# M220A.net
KiCad netlist of a schematic drawn in EAGLE
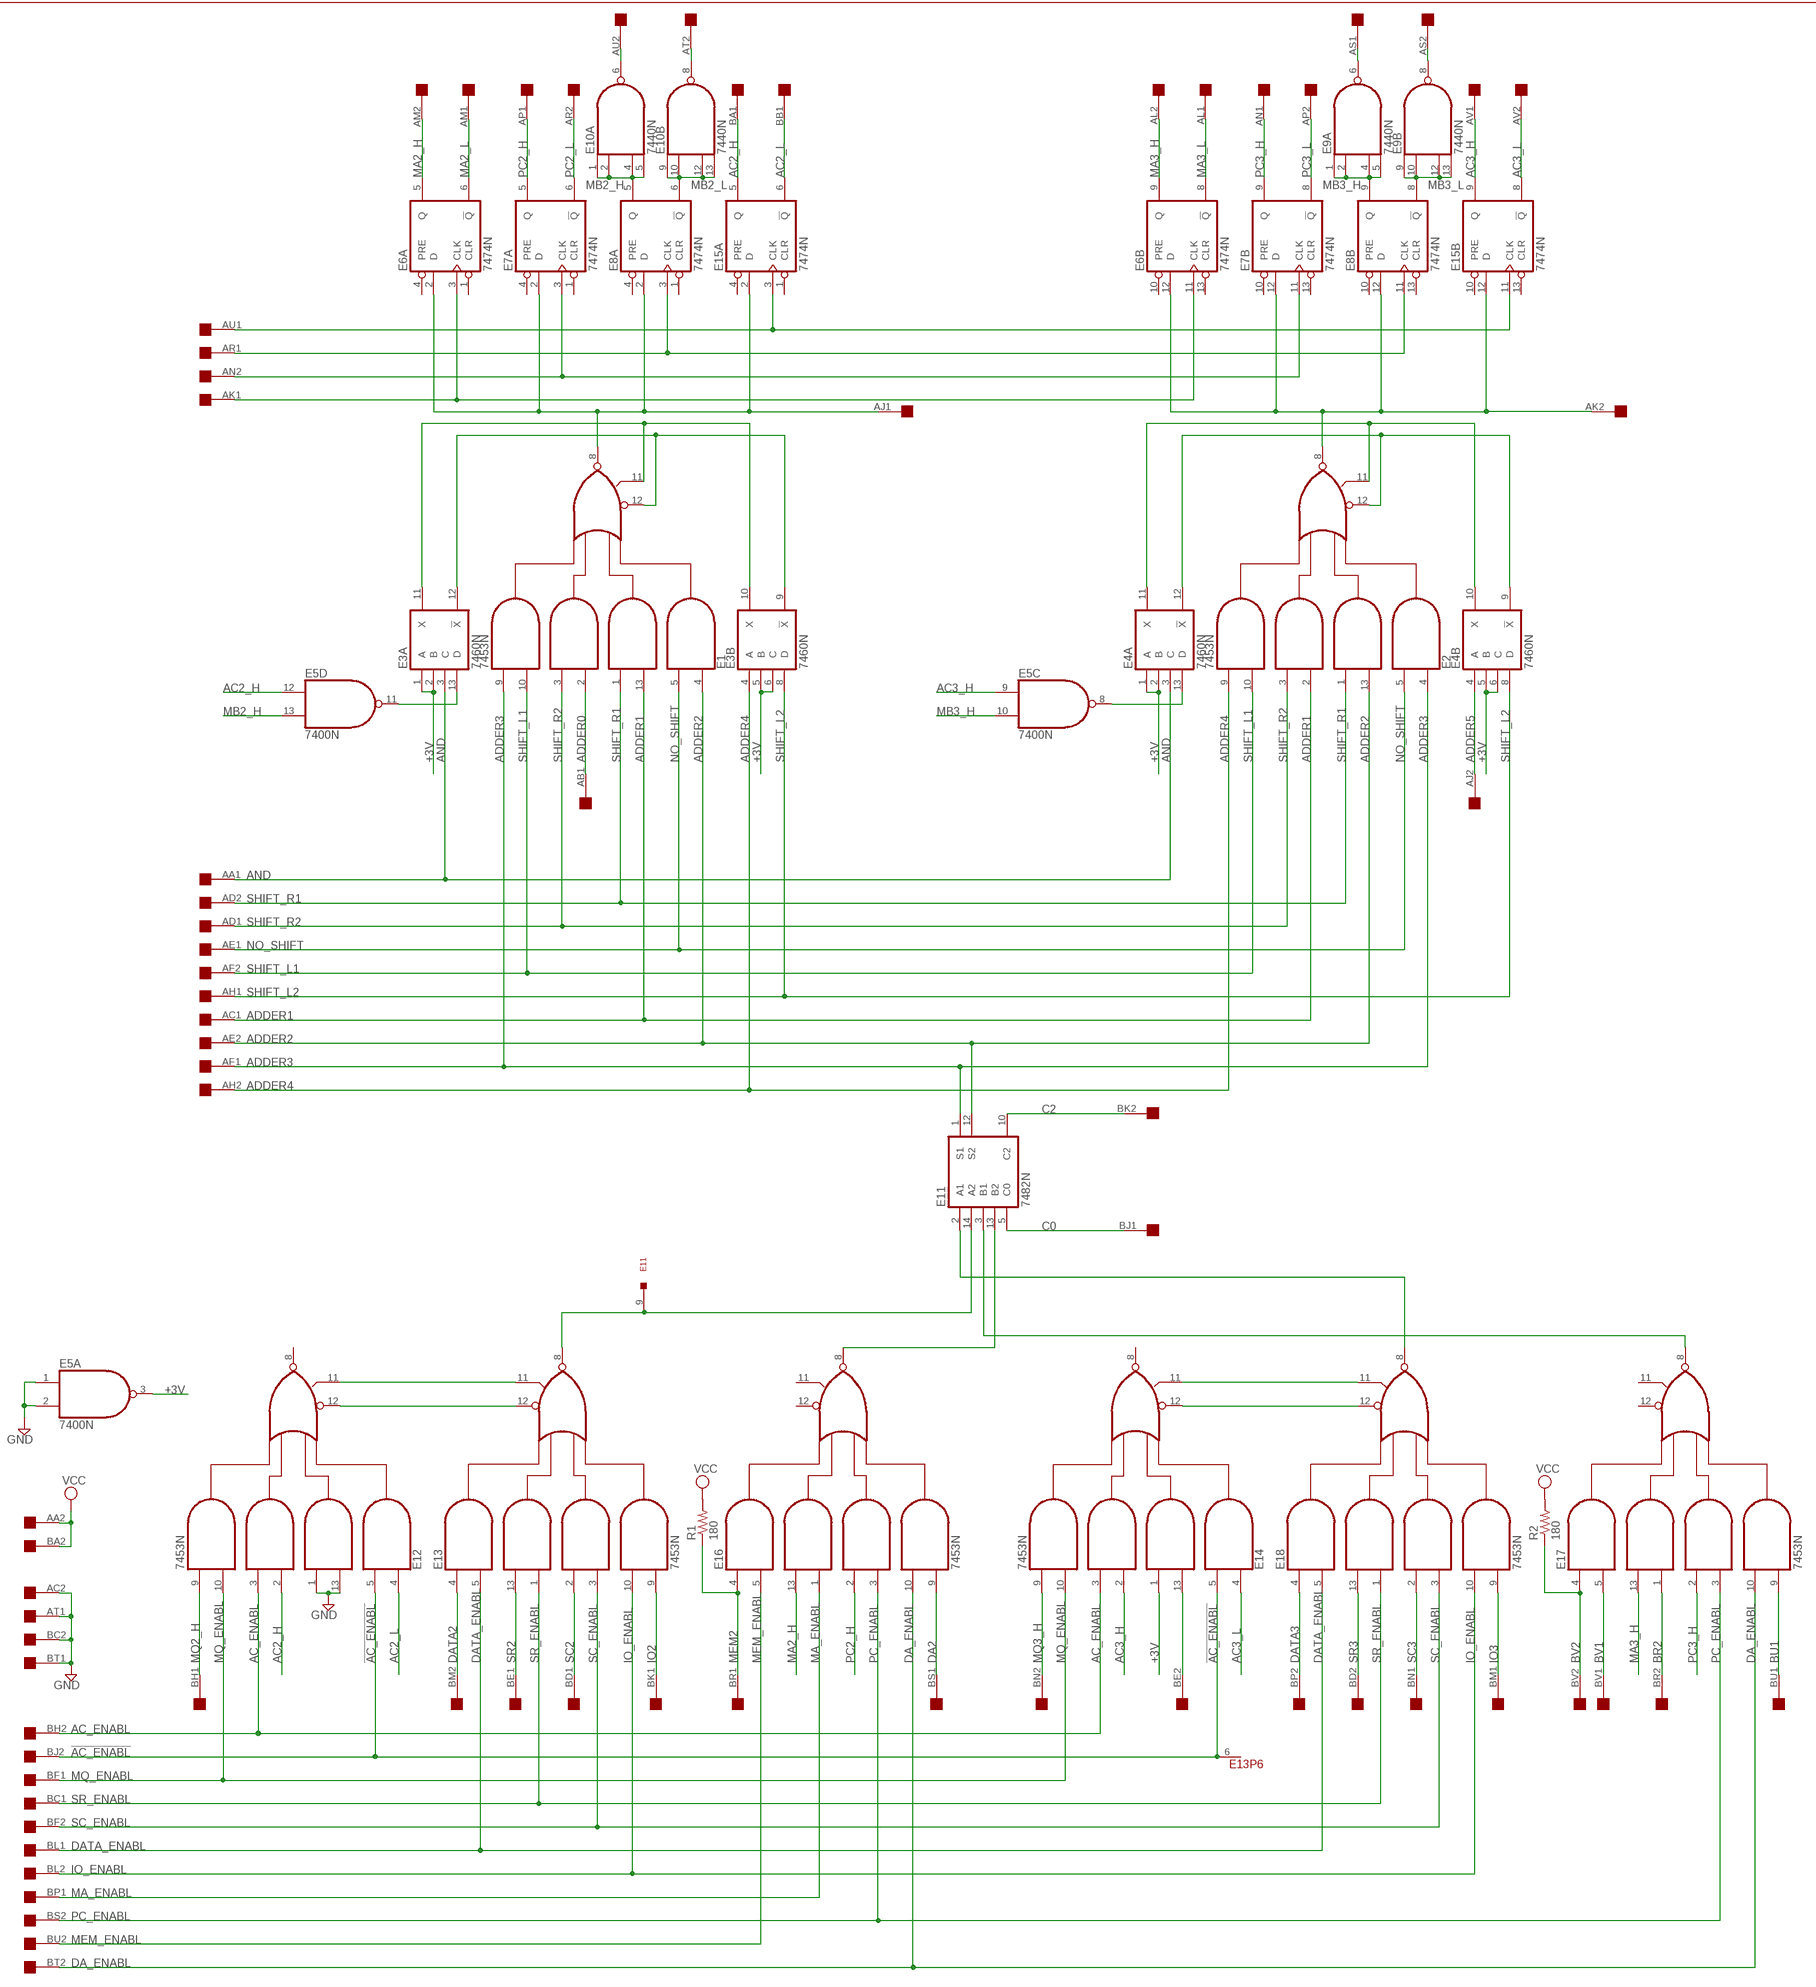
[diagram p0: schematic, sheet 1, part 1 of 2]
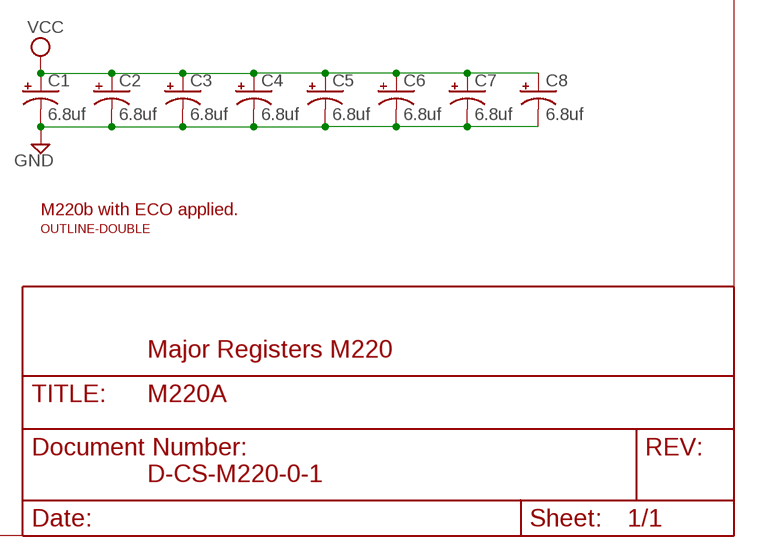
[diagram p1: schematic, sheet 1, part 2 of 2]

(export (version "E")
  (design (tool "Eeschema 10.0.6"))
  (components
    (comp (ref "C1")
      (value "6.8uf")
      (footprint "eagle-import:E15-5")
      (libsource (lib "eagle-import") (part "CPOL-USE15-5AXIAL"))
    )
    (comp (ref "C2")
      (value "6.8uf")
      (footprint "eagle-import:E15-5")
      (libsource (lib "eagle-import") (part "CPOL-USE15-5AXIAL"))
    )
    (comp (ref "C3")
      (value "6.8uf")
      (footprint "eagle-import:E15-5")
      (libsource (lib "eagle-import") (part "CPOL-USE15-5AXIAL"))
    )
    (comp (ref "C4")
      (value "6.8uf")
      (footprint "eagle-import:E15-5")
      (libsource (lib "eagle-import") (part "CPOL-USE15-5AXIAL"))
    )
    (comp (ref "C5")
      (value "6.8uf")
      (footprint "eagle-import:E15-5")
      (libsource (lib "eagle-import") (part "CPOL-USE15-5AXIAL"))
    )
    (comp (ref "C6")
      (value "6.8uf")
      (footprint "eagle-import:E15-5")
      (libsource (lib "eagle-import") (part "CPOL-USE15-5AXIAL"))
    )
    (comp (ref "C7")
      (value "6.8uf")
      (footprint "eagle-import:E15-5")
      (libsource (lib "eagle-import") (part "CPOL-USE15-5AXIAL"))
    )
    (comp (ref "C8")
      (value "6.8uf")
      (footprint "eagle-import:E15-5")
      (libsource (lib "eagle-import") (part "CPOL-USE15-5AXIAL"))
    )
    (comp (ref "E1")
      (value "7453N")
      (footprint "eagle-import:DIL14")
      (libsource (lib "eagle-import") (part "7453N"))
    )
    (comp (ref "E2")
      (value "7453N")
      (footprint "eagle-import:DIL14")
      (libsource (lib "eagle-import") (part "7453N"))
    )
    (comp (ref "E3")
      (value "7460N")
      (footprint "eagle-import:DIL14")
      (libsource (lib "eagle-import") (part "7460N"))
    )
    (comp (ref "E4")
      (value "7460N")
      (footprint "eagle-import:DIL14")
      (libsource (lib "eagle-import") (part "7460N"))
    )
    (comp (ref "E5")
      (value "7400N")
      (footprint "eagle-import:DIL14")
      (libsource (lib "eagle-import") (part "7400N"))
    )
    (comp (ref "E6")
      (value "7474N")
      (footprint "eagle-import:DIL14")
      (libsource (lib "eagle-import") (part "7474NS"))
    )
    (comp (ref "E7")
      (value "7474N")
      (footprint "eagle-import:DIL14")
      (libsource (lib "eagle-import") (part "7474NS"))
    )
    (comp (ref "E8")
      (value "7474N")
      (footprint "eagle-import:DIL14")
      (libsource (lib "eagle-import") (part "7474NS"))
    )
    (comp (ref "E9")
      (value "7440N")
      (footprint "eagle-import:DIL14")
      (libsource (lib "eagle-import") (part "7420NS"))
    )
    (comp (ref "E10")
      (value "7440N")
      (footprint "eagle-import:DIL14")
      (libsource (lib "eagle-import") (part "7420NS"))
    )
    (comp (ref "E11")
      (value "7482N")
      (footprint "eagle-import:DIL14")
      (libsource (lib "eagle-import") (part "7482N"))
    )
    (comp (ref "E12")
      (value "7453N")
      (footprint "eagle-import:DIL14")
      (libsource (lib "eagle-import") (part "7453N"))
    )
    (comp (ref "E13")
      (value "7453N")
      (footprint "eagle-import:DIL14")
      (libsource (lib "eagle-import") (part "7453N"))
    )
    (comp (ref "E14")
      (value "7453N")
      (footprint "eagle-import:DIL14")
      (libsource (lib "eagle-import") (part "7453N"))
    )
    (comp (ref "E15")
      (value "7474N")
      (footprint "eagle-import:DIL14")
      (libsource (lib "eagle-import") (part "7474NS"))
    )
    (comp (ref "E16")
      (value "7453N")
      (footprint "eagle-import:DIL14")
      (libsource (lib "eagle-import") (part "7453N"))
    )
    (comp (ref "E17")
      (value "7453N")
      (footprint "eagle-import:DIL14")
      (libsource (lib "eagle-import") (part "7453N"))
    )
    (comp (ref "E18")
      (value "7453N")
      (footprint "eagle-import:DIL14")
      (libsource (lib "eagle-import") (part "7453N"))
    )
    (comp (ref "R1")
      (value "180")
      (footprint "eagle-import:0207_10")
      (libsource (lib "eagle-import") (part "R-US_0207/10"))
    )
    (comp (ref "R2")
      (value "180")
      (footprint "eagle-import:0207_10")
      (libsource (lib "eagle-import") (part "R-US_0207/10"))
    )
    (comp (ref "U$1")
      (value "DOUBLE")
      (footprint "eagle-import:EDGE-CON4")
      (libsource (lib "eagle-import") (part "DOUBLE"))
    )
    (comp (ref "U$2")
      (value "OUTLINE-DOUBLE")
      (footprint "eagle-import:DOUBLE")
      (libsource (lib "eagle-import") (part "OUTLINE-DOUBLE"))
    )
  )
  (nets
    (net (code "1") (name "/+3V") (class "Default")
      (node (ref "E14") (pin "1") (pinfunction "I4_1") (pintype "input"))
      (node (ref "E3") (pin "1") (pinfunction "A_1") (pintype "input"))
      (node (ref "E3") (pin "2") (pinfunction "B_2") (pintype "input"))
      (node (ref "E3") (pin "5") (pinfunction "B_5") (pintype "input"))
      (node (ref "E3") (pin "6") (pinfunction "C_6") (pintype "input"))
      (node (ref "E4") (pin "1") (pinfunction "A_1") (pintype "input"))
      (node (ref "E4") (pin "2") (pinfunction "B_2") (pintype "input"))
      (node (ref "E4") (pin "5") (pinfunction "B_5") (pintype "input"))
      (node (ref "E4") (pin "6") (pinfunction "C_6") (pintype "input"))
      (node (ref "E5") (pin "3") (pinfunction "O_3") (pintype "output"))
    )
    (net (code "2") (name "/AC2_H") (class "Default")
      (node (ref "E12") (pin "2") (pinfunction "I5_2") (pintype "input"))
      (node (ref "E15") (pin "5") (pinfunction "Q_5") (pintype "output"))
      (node (ref "E5") (pin "12") (pinfunction "I0_12") (pintype "input"))
      (node (ref "U$1") (pin "BA1") (pinfunction "1_BA1") (pintype "bidirectional"))
    )
    (net (code "3") (name "/AC2_L") (class "Default")
      (node (ref "E12") (pin "4") (pinfunction "I1_4") (pintype "input"))
      (node (ref "E15") (pin "6") (pinfunction "~{Q}_6") (pintype "output"))
      (node (ref "U$1") (pin "BB1") (pinfunction "1_BB1") (pintype "bidirectional"))
    )
    (net (code "4") (name "/AC3_H") (class "Default")
      (node (ref "E14") (pin "2") (pinfunction "I5_2") (pintype "input"))
      (node (ref "E15") (pin "9") (pinfunction "Q_9") (pintype "output"))
      (node (ref "E5") (pin "9") (pinfunction "I0_9") (pintype "input"))
      (node (ref "U$1") (pin "AV1") (pinfunction "1_AV1") (pintype "bidirectional"))
    )
    (net (code "5") (name "/AC3_L") (class "Default")
      (node (ref "E14") (pin "4") (pinfunction "I1_4") (pintype "input"))
      (node (ref "E15") (pin "8") (pinfunction "~{Q}_8") (pintype "output"))
      (node (ref "U$1") (pin "AV2") (pinfunction "1_AV2") (pintype "bidirectional"))
    )
    (net (code "6") (name "/AC_ENABL") (class "Default")
      (node (ref "E12") (pin "3") (pinfunction "I6_3") (pintype "input"))
      (node (ref "E14") (pin "3") (pinfunction "I6_3") (pintype "input"))
      (node (ref "U$1") (pin "BH2") (pinfunction "1_BH2") (pintype "bidirectional"))
    )
    (net (code "7") (name "/ADDER0") (class "Default")
      (node (ref "E1") (pin "2") (pinfunction "I5_2") (pintype "input"))
      (node (ref "U$1") (pin "AB1") (pinfunction "1_AB1") (pintype "bidirectional"))
    )
    (net (code "8") (name "/ADDER1") (class "Default")
      (node (ref "E1") (pin "13") (pinfunction "I3_13") (pintype "input"))
      (node (ref "E2") (pin "2") (pinfunction "I5_2") (pintype "input"))
      (node (ref "U$1") (pin "AC1") (pinfunction "1_AC1") (pintype "bidirectional"))
    )
    (net (code "9") (name "/ADDER2") (class "Default")
      (node (ref "E1") (pin "4") (pinfunction "I1_4") (pintype "input"))
      (node (ref "E11") (pin "12") (pinfunction "S2_12") (pintype "output"))
      (node (ref "E2") (pin "13") (pinfunction "I3_13") (pintype "input"))
      (node (ref "U$1") (pin "AE2") (pinfunction "1_AE2") (pintype "bidirectional"))
    )
    (net (code "10") (name "/ADDER3") (class "Default")
      (node (ref "E1") (pin "9") (pinfunction "I8_9") (pintype "input"))
      (node (ref "E11") (pin "1") (pinfunction "S1_1") (pintype "output"))
      (node (ref "E2") (pin "4") (pinfunction "I1_4") (pintype "input"))
      (node (ref "U$1") (pin "AF1") (pinfunction "1_AF1") (pintype "bidirectional"))
    )
    (net (code "11") (name "/ADDER4") (class "Default")
      (node (ref "E2") (pin "9") (pinfunction "I8_9") (pintype "input"))
      (node (ref "E3") (pin "4") (pinfunction "A_4") (pintype "input"))
      (node (ref "U$1") (pin "AH2") (pinfunction "1_AH2") (pintype "bidirectional"))
    )
    (net (code "12") (name "/ADDER5") (class "Default")
      (node (ref "E4") (pin "4") (pinfunction "A_4") (pintype "input"))
      (node (ref "U$1") (pin "AJ2") (pinfunction "1_AJ2") (pintype "bidirectional"))
    )
    (net (code "13") (name "/AND") (class "Default")
      (node (ref "E3") (pin "3") (pinfunction "C_3") (pintype "input"))
      (node (ref "E4") (pin "3") (pinfunction "C_3") (pintype "input"))
      (node (ref "U$1") (pin "AA1") (pinfunction "1_AA1") (pintype "bidirectional"))
    )
    (net (code "14") (name "/BR2") (class "Default")
      (node (ref "E17") (pin "1") (pinfunction "I4_1") (pintype "input"))
      (node (ref "U$1") (pin "BR2") (pinfunction "1_BR2") (pintype "bidirectional"))
    )
    (net (code "15") (name "/BU1") (class "Default")
      (node (ref "E17") (pin "9") (pinfunction "I8_9") (pintype "input"))
      (node (ref "U$1") (pin "BU1") (pinfunction "1_BU1") (pintype "bidirectional"))
    )
    (net (code "16") (name "/BV1") (class "Default")
      (node (ref "E17") (pin "5") (pinfunction "I2_5") (pintype "input"))
      (node (ref "U$1") (pin "BV1") (pinfunction "1_BV1") (pintype "bidirectional"))
    )
    (net (code "17") (name "/BV2") (class "Default")
      (node (ref "E17") (pin "4") (pinfunction "I1_4") (pintype "input"))
      (node (ref "R2") (pin "1") (pinfunction "1_1") (pintype "passive"))
      (node (ref "U$1") (pin "BV2") (pinfunction "1_BV2") (pintype "bidirectional"))
    )
    (net (code "18") (name "/C0") (class "Default")
      (node (ref "E11") (pin "5") (pinfunction "C0_5") (pintype "input"))
      (node (ref "U$1") (pin "BJ1") (pinfunction "1_BJ1") (pintype "bidirectional"))
    )
    (net (code "19") (name "/C2") (class "Default")
      (node (ref "E11") (pin "10") (pinfunction "C2_10") (pintype "output"))
      (node (ref "U$1") (pin "BK2") (pinfunction "1_BK2") (pintype "bidirectional"))
    )
    (net (code "20") (name "/DA2") (class "Default")
      (node (ref "E16") (pin "9") (pinfunction "I8_9") (pintype "input"))
      (node (ref "U$1") (pin "BS1") (pinfunction "1_BS1") (pintype "bidirectional"))
    )
    (net (code "21") (name "/DATA2") (class "Default")
      (node (ref "E13") (pin "4") (pinfunction "I1_4") (pintype "input"))
      (node (ref "U$1") (pin "BM2") (pinfunction "1_BM2") (pintype "bidirectional"))
    )
    (net (code "22") (name "/DATA3") (class "Default")
      (node (ref "E18") (pin "4") (pinfunction "I1_4") (pintype "input"))
      (node (ref "U$1") (pin "BP2") (pinfunction "1_BP2") (pintype "bidirectional"))
    )
    (net (code "23") (name "/DATA_ENABL") (class "Default")
      (node (ref "E13") (pin "5") (pinfunction "I2_5") (pintype "input"))
      (node (ref "E18") (pin "5") (pinfunction "I2_5") (pintype "input"))
      (node (ref "U$1") (pin "BL1") (pinfunction "1_BL1") (pintype "bidirectional"))
    )
    (net (code "24") (name "/DA_ENABL") (class "Default")
      (node (ref "E16") (pin "10") (pinfunction "I7_10") (pintype "input"))
      (node (ref "E17") (pin "10") (pinfunction "I7_10") (pintype "input"))
      (node (ref "U$1") (pin "BT2") (pinfunction "1_BT2") (pintype "bidirectional"))
    )
    (net (code "25") (name "/IO2") (class "Default")
      (node (ref "E13") (pin "9") (pinfunction "I8_9") (pintype "input"))
      (node (ref "U$1") (pin "BK1") (pinfunction "1_BK1") (pintype "bidirectional"))
    )
    (net (code "26") (name "/IO3") (class "Default")
      (node (ref "E18") (pin "9") (pinfunction "I8_9") (pintype "input"))
      (node (ref "U$1") (pin "BM1") (pinfunction "1_BM1") (pintype "bidirectional"))
    )
    (net (code "27") (name "/IO_ENABL") (class "Default")
      (node (ref "E13") (pin "10") (pinfunction "I7_10") (pintype "input"))
      (node (ref "E18") (pin "10") (pinfunction "I7_10") (pintype "input"))
      (node (ref "U$1") (pin "BL2") (pinfunction "1_BL2") (pintype "bidirectional"))
    )
    (net (code "28") (name "/MA2_H") (class "Default")
      (node (ref "E16") (pin "13") (pinfunction "I3_13") (pintype "input"))
      (node (ref "E6") (pin "5") (pinfunction "Q_5") (pintype "output"))
      (node (ref "U$1") (pin "AM2") (pinfunction "1_AM2") (pintype "bidirectional"))
    )
    (net (code "29") (name "/MA2_L") (class "Default")
      (node (ref "E6") (pin "6") (pinfunction "~{Q}_6") (pintype "output"))
      (node (ref "U$1") (pin "AM1") (pinfunction "1_AM1") (pintype "bidirectional"))
    )
    (net (code "30") (name "/MA3_H") (class "Default")
      (node (ref "E17") (pin "13") (pinfunction "I3_13") (pintype "input"))
      (node (ref "E6") (pin "9") (pinfunction "Q_9") (pintype "output"))
      (node (ref "U$1") (pin "AL2") (pinfunction "1_AL2") (pintype "bidirectional"))
    )
    (net (code "31") (name "/MA3_L") (class "Default")
      (node (ref "E6") (pin "8") (pinfunction "~{Q}_8") (pintype "output"))
      (node (ref "U$1") (pin "AL1") (pinfunction "1_AL1") (pintype "bidirectional"))
    )
    (net (code "32") (name "/MA_ENABL") (class "Default")
      (node (ref "E16") (pin "1") (pinfunction "I4_1") (pintype "input"))
      (node (ref "U$1") (pin "BP1") (pinfunction "1_BP1") (pintype "bidirectional"))
    )
    (net (code "33") (name "/MB2_H") (class "Default")
      (node (ref "E10") (pin "1") (pinfunction "I0_1") (pintype "input"))
      (node (ref "E10") (pin "2") (pinfunction "I1_2") (pintype "input"))
      (node (ref "E10") (pin "4") (pinfunction "I2_4") (pintype "input"))
      (node (ref "E10") (pin "5") (pinfunction "I3_5") (pintype "input"))
      (node (ref "E5") (pin "13") (pinfunction "I1_13") (pintype "input"))
      (node (ref "E8") (pin "5") (pinfunction "Q_5") (pintype "output"))
    )
    (net (code "34") (name "/MB2_L") (class "Default")
      (node (ref "E10") (pin "10") (pinfunction "I1_10") (pintype "input"))
      (node (ref "E10") (pin "12") (pinfunction "I2_12") (pintype "input"))
      (node (ref "E10") (pin "13") (pinfunction "I3_13") (pintype "input"))
      (node (ref "E10") (pin "9") (pinfunction "I0_9") (pintype "input"))
      (node (ref "E8") (pin "6") (pinfunction "~{Q}_6") (pintype "output"))
    )
    (net (code "35") (name "/MB3_H") (class "Default")
      (node (ref "E5") (pin "10") (pinfunction "I1_10") (pintype "input"))
      (node (ref "E8") (pin "9") (pinfunction "Q_9") (pintype "output"))
      (node (ref "E9") (pin "1") (pinfunction "I0_1") (pintype "input"))
      (node (ref "E9") (pin "2") (pinfunction "I1_2") (pintype "input"))
      (node (ref "E9") (pin "4") (pinfunction "I2_4") (pintype "input"))
      (node (ref "E9") (pin "5") (pinfunction "I3_5") (pintype "input"))
    )
    (net (code "36") (name "/MB3_L") (class "Default")
      (node (ref "E8") (pin "8") (pinfunction "~{Q}_8") (pintype "output"))
      (node (ref "E9") (pin "10") (pinfunction "I1_10") (pintype "input"))
      (node (ref "E9") (pin "12") (pinfunction "I2_12") (pintype "input"))
      (node (ref "E9") (pin "13") (pinfunction "I3_13") (pintype "input"))
      (node (ref "E9") (pin "9") (pinfunction "I0_9") (pintype "input"))
    )
    (net (code "37") (name "/MEM2") (class "Default")
      (node (ref "E16") (pin "4") (pinfunction "I1_4") (pintype "input"))
      (node (ref "R1") (pin "1") (pinfunction "1_1") (pintype "passive"))
      (node (ref "U$1") (pin "BR1") (pinfunction "1_BR1") (pintype "bidirectional"))
    )
    (net (code "38") (name "/MEM_ENABL") (class "Default")
      (node (ref "E16") (pin "5") (pinfunction "I2_5") (pintype "input"))
      (node (ref "U$1") (pin "BU2") (pinfunction "1_BU2") (pintype "bidirectional"))
    )
    (net (code "39") (name "/MQ2_H") (class "Default")
      (node (ref "E12") (pin "9") (pinfunction "I8_9") (pintype "input"))
      (node (ref "U$1") (pin "BH1") (pinfunction "1_BH1") (pintype "bidirectional"))
    )
    (net (code "40") (name "/MQ3_H") (class "Default")
      (node (ref "E14") (pin "9") (pinfunction "I8_9") (pintype "input"))
      (node (ref "U$1") (pin "BN2") (pinfunction "1_BN2") (pintype "bidirectional"))
    )
    (net (code "41") (name "/MQ_ENABL") (class "Default")
      (node (ref "E12") (pin "10") (pinfunction "I7_10") (pintype "input"))
      (node (ref "E14") (pin "10") (pinfunction "I7_10") (pintype "input"))
      (node (ref "U$1") (pin "BF1") (pinfunction "1_BF1") (pintype "bidirectional"))
    )
    (net (code "42") (name "/NO_SHIFT") (class "Default")
      (node (ref "E1") (pin "5") (pinfunction "I2_5") (pintype "input"))
      (node (ref "E2") (pin "5") (pinfunction "I2_5") (pintype "input"))
      (node (ref "U$1") (pin "AE1") (pinfunction "1_AE1") (pintype "bidirectional"))
    )
    (net (code "43") (name "/PC2_H") (class "Default")
      (node (ref "E16") (pin "2") (pinfunction "I5_2") (pintype "input"))
      (node (ref "E7") (pin "5") (pinfunction "Q_5") (pintype "output"))
      (node (ref "U$1") (pin "AP1") (pinfunction "1_AP1") (pintype "bidirectional"))
    )
    (net (code "44") (name "/PC2_L") (class "Default")
      (node (ref "E7") (pin "6") (pinfunction "~{Q}_6") (pintype "output"))
      (node (ref "U$1") (pin "AR2") (pinfunction "1_AR2") (pintype "bidirectional"))
    )
    (net (code "45") (name "/PC3_H") (class "Default")
      (node (ref "E17") (pin "2") (pinfunction "I5_2") (pintype "input"))
      (node (ref "E7") (pin "9") (pinfunction "Q_9") (pintype "output"))
      (node (ref "U$1") (pin "AN1") (pinfunction "1_AN1") (pintype "bidirectional"))
    )
    (net (code "46") (name "/PC3_L") (class "Default")
      (node (ref "E7") (pin "8") (pinfunction "~{Q}_8") (pintype "output"))
      (node (ref "U$1") (pin "AP2") (pinfunction "1_AP2") (pintype "bidirectional"))
    )
    (net (code "47") (name "/PC_ENABL") (class "Default")
      (node (ref "E16") (pin "3") (pinfunction "I6_3") (pintype "input"))
      (node (ref "E17") (pin "3") (pinfunction "I6_3") (pintype "input"))
      (node (ref "U$1") (pin "BS2") (pinfunction "1_BS2") (pintype "bidirectional"))
    )
    (net (code "48") (name "/SC2") (class "Default")
      (node (ref "E13") (pin "2") (pinfunction "I5_2") (pintype "input"))
      (node (ref "U$1") (pin "BD1") (pinfunction "1_BD1") (pintype "bidirectional"))
    )
    (net (code "49") (name "/SC3") (class "Default")
      (node (ref "E18") (pin "2") (pinfunction "I5_2") (pintype "input"))
      (node (ref "U$1") (pin "BN1") (pinfunction "1_BN1") (pintype "bidirectional"))
    )
    (net (code "50") (name "/SC_ENABL") (class "Default")
      (node (ref "E13") (pin "3") (pinfunction "I6_3") (pintype "input"))
      (node (ref "E18") (pin "3") (pinfunction "I6_3") (pintype "input"))
      (node (ref "U$1") (pin "BF2") (pinfunction "1_BF2") (pintype "bidirectional"))
    )
    (net (code "51") (name "/SHIFT_L1") (class "Default")
      (node (ref "E1") (pin "10") (pinfunction "I7_10") (pintype "input"))
      (node (ref "E2") (pin "10") (pinfunction "I7_10") (pintype "input"))
      (node (ref "U$1") (pin "AF2") (pinfunction "1_AF2") (pintype "bidirectional"))
    )
    (net (code "52") (name "/SHIFT_L2") (class "Default")
      (node (ref "E3") (pin "8") (pinfunction "D_8") (pintype "input"))
      (node (ref "E4") (pin "8") (pinfunction "D_8") (pintype "input"))
      (node (ref "U$1") (pin "AH1") (pinfunction "1_AH1") (pintype "bidirectional"))
    )
    (net (code "53") (name "/SHIFT_R1") (class "Default")
      (node (ref "E1") (pin "1") (pinfunction "I4_1") (pintype "input"))
      (node (ref "E2") (pin "1") (pinfunction "I4_1") (pintype "input"))
      (node (ref "U$1") (pin "AD2") (pinfunction "1_AD2") (pintype "bidirectional"))
    )
    (net (code "54") (name "/SHIFT_R2") (class "Default")
      (node (ref "E1") (pin "3") (pinfunction "I6_3") (pintype "input"))
      (node (ref "E2") (pin "3") (pinfunction "I6_3") (pintype "input"))
      (node (ref "U$1") (pin "AD1") (pinfunction "1_AD1") (pintype "bidirectional"))
    )
    (net (code "55") (name "/SR2") (class "Default")
      (node (ref "E13") (pin "13") (pinfunction "I3_13") (pintype "input"))
      (node (ref "U$1") (pin "BE1") (pinfunction "1_BE1") (pintype "bidirectional"))
    )
    (net (code "56") (name "/SR3") (class "Default")
      (node (ref "E18") (pin "13") (pinfunction "I3_13") (pintype "input"))
      (node (ref "U$1") (pin "BD2") (pinfunction "1_BD2") (pintype "bidirectional"))
    )
    (net (code "57") (name "/SR_ENABL") (class "Default")
      (node (ref "E13") (pin "1") (pinfunction "I4_1") (pintype "input"))
      (node (ref "E18") (pin "1") (pinfunction "I4_1") (pintype "input"))
      (node (ref "U$1") (pin "BC1") (pinfunction "1_BC1") (pintype "bidirectional"))
    )
    (net (code "58") (name "/~{AC_ENABL}") (class "Default")
      (node (ref "E12") (pin "5") (pinfunction "I2_5") (pintype "input"))
      (node (ref "E13") (pin "6") (pinfunction "SPARE_6") (pintype "passive"))
      (node (ref "E14") (pin "5") (pinfunction "I2_5") (pintype "input"))
      (node (ref "U$1") (pin "BJ2") (pinfunction "1_BJ2") (pintype "bidirectional"))
    )
    (net (code "59") (name "GND") (class "Default")
      (node (ref "C1") (pin "-") (pinfunction "-_-") (pintype "passive"))
      (node (ref "C2") (pin "-") (pinfunction "-_-") (pintype "passive"))
      (node (ref "C3") (pin "-") (pinfunction "-_-") (pintype "passive"))
      (node (ref "C4") (pin "-") (pinfunction "-_-") (pintype "passive"))
      (node (ref "C5") (pin "-") (pinfunction "-_-") (pintype "passive"))
      (node (ref "C6") (pin "-") (pinfunction "-_-") (pintype "passive"))
      (node (ref "C7") (pin "-") (pinfunction "-_-") (pintype "passive"))
      (node (ref "C8") (pin "-") (pinfunction "-_-") (pintype "passive"))
      (node (ref "E12") (pin "1") (pinfunction "I4_1") (pintype "input"))
      (node (ref "E12") (pin "13") (pinfunction "I3_13") (pintype "input"))
      (node (ref "E5") (pin "1") (pinfunction "I0_1") (pintype "input"))
      (node (ref "E5") (pin "2") (pinfunction "I1_2") (pintype "input"))
      (node (ref "U$1") (pin "AC2") (pinfunction "1_AC2") (pintype "bidirectional"))
      (node (ref "U$1") (pin "AT1") (pinfunction "1_AT1") (pintype "bidirectional"))
      (node (ref "U$1") (pin "BC2") (pinfunction "1_BC2") (pintype "bidirectional"))
      (node (ref "U$1") (pin "BT1") (pinfunction "1_BT1") (pintype "bidirectional"))
    )
    (net (code "60") (name "Net-(E1A-I9)") (class "Default")
      (node (ref "E1") (pin "12") (pinfunction "I9_12") (pintype "passive"))
      (node (ref "E3") (pin "12") (pinfunction "~{X}_12") (pintype "output"))
      (node (ref "E3") (pin "9") (pinfunction "~{X}_9") (pintype "output"))
    )
    (net (code "61") (name "Net-(E1A-I10)") (class "Default")
      (node (ref "E1") (pin "11") (pinfunction "I10_11") (pintype "passive"))
      (node (ref "E3") (pin "10") (pinfunction "X_10") (pintype "output"))
      (node (ref "E3") (pin "11") (pinfunction "X_11") (pintype "output"))
    )
    (net (code "62") (name "Net-(E2A-I9)") (class "Default")
      (node (ref "E2") (pin "12") (pinfunction "I9_12") (pintype "passive"))
      (node (ref "E4") (pin "12") (pinfunction "~{X}_12") (pintype "output"))
      (node (ref "E4") (pin "9") (pinfunction "~{X}_9") (pintype "output"))
    )
    (net (code "63") (name "Net-(E2A-I10)") (class "Default")
      (node (ref "E2") (pin "11") (pinfunction "I10_11") (pintype "passive"))
      (node (ref "E4") (pin "10") (pinfunction "X_10") (pintype "output"))
      (node (ref "E4") (pin "11") (pinfunction "X_11") (pintype "output"))
    )
    (net (code "64") (name "Net-(E3A-D)") (class "Default")
      (node (ref "E3") (pin "13") (pinfunction "D_13") (pintype "input"))
      (node (ref "E5") (pin "11") (pinfunction "O_11") (pintype "output"))
    )
    (net (code "65") (name "Net-(E4A-D)") (class "Default")
      (node (ref "E4") (pin "13") (pinfunction "D_13") (pintype "input"))
      (node (ref "E5") (pin "8") (pinfunction "O_8") (pintype "output"))
    )
    (net (code "66") (name "Net-(E6A-CLK)") (class "Default")
      (node (ref "E6") (pin "11") (pinfunction "CLK_11") (pintype "input"))
      (node (ref "E6") (pin "3") (pinfunction "CLK_3") (pintype "input"))
      (node (ref "U$1") (pin "AK1") (pinfunction "1_AK1") (pintype "bidirectional"))
    )
    (net (code "67") (name "Net-(E7A-CLK)") (class "Default")
      (node (ref "E7") (pin "11") (pinfunction "CLK_11") (pintype "input"))
      (node (ref "E7") (pin "3") (pinfunction "CLK_3") (pintype "input"))
      (node (ref "U$1") (pin "AN2") (pinfunction "1_AN2") (pintype "bidirectional"))
    )
    (net (code "68") (name "Net-(E8A-CLK)") (class "Default")
      (node (ref "E8") (pin "11") (pinfunction "CLK_11") (pintype "input"))
      (node (ref "E8") (pin "3") (pinfunction "CLK_3") (pintype "input"))
      (node (ref "U$1") (pin "AR1") (pinfunction "1_AR1") (pintype "bidirectional"))
    )
    (net (code "69") (name "Net-(E9A-O)") (class "Default")
      (node (ref "E9") (pin "6") (pinfunction "O_6") (pintype "output"))
      (node (ref "U$1") (pin "AS1") (pinfunction "1_AS1") (pintype "bidirectional"))
    )
    (net (code "70") (name "Net-(E9B-O)") (class "Default")
      (node (ref "E9") (pin "8") (pinfunction "O_8") (pintype "output"))
      (node (ref "U$1") (pin "AS2") (pinfunction "1_AS2") (pintype "bidirectional"))
    )
    (net (code "71") (name "Net-(E10A-O)") (class "Default")
      (node (ref "E10") (pin "6") (pinfunction "O_6") (pintype "output"))
      (node (ref "U$1") (pin "AU2") (pinfunction "1_AU2") (pintype "bidirectional"))
    )
    (net (code "72") (name "Net-(E10B-O)") (class "Default")
      (node (ref "E10") (pin "8") (pinfunction "O_8") (pintype "output"))
      (node (ref "U$1") (pin "AT2") (pinfunction "1_AT2") (pintype "bidirectional"))
    )
    (net (code "73") (name "Net-(E11D-P$2)") (class "Default")
      (node (ref "E11") (pin "14") (pinfunction "A2_14") (pintype "input"))
      (node (ref "E11") (pin "9") (pinfunction "P$2_9") (pintype "passive"))
      (node (ref "E13") (pin "8") (pinfunction "O_8") (pintype "output"))
    )
    (net (code "74") (name "Net-(E11E-A1)") (class "Default")
      (node (ref "E11") (pin "2") (pinfunction "A1_2") (pintype "input"))
      (node (ref "E18") (pin "8") (pinfunction "O_8") (pintype "output"))
    )
    (net (code "75") (name "Net-(E11E-B1)") (class "Default")
      (node (ref "E11") (pin "3") (pinfunction "B1_3") (pintype "input"))
      (node (ref "E17") (pin "8") (pinfunction "O_8") (pintype "output"))
    )
    (net (code "76") (name "Net-(E11E-B2)") (class "Default")
      (node (ref "E11") (pin "13") (pinfunction "B2_13") (pintype "input"))
      (node (ref "E16") (pin "8") (pinfunction "O_8") (pintype "output"))
    )
    (net (code "77") (name "Net-(E12A-I9)") (class "Default")
      (node (ref "E12") (pin "12") (pinfunction "I9_12") (pintype "passive"))
      (node (ref "E13") (pin "12") (pinfunction "I9_12") (pintype "passive"))
    )
    (net (code "78") (name "Net-(E12A-I10)") (class "Default")
      (node (ref "E12") (pin "11") (pinfunction "I10_11") (pintype "passive"))
      (node (ref "E13") (pin "11") (pinfunction "I10_11") (pintype "passive"))
    )
    (net (code "79") (name "Net-(E14A-I3)") (class "Default")
      (node (ref "E14") (pin "13") (pinfunction "I3_13") (pintype "input"))
      (node (ref "U$1") (pin "BE2") (pinfunction "1_BE2") (pintype "bidirectional"))
    )
    (net (code "80") (name "Net-(E14A-I9)") (class "Default")
      (node (ref "E14") (pin "12") (pinfunction "I9_12") (pintype "passive"))
      (node (ref "E18") (pin "12") (pinfunction "I9_12") (pintype "passive"))
    )
    (net (code "81") (name "Net-(E14A-I10)") (class "Default")
      (node (ref "E14") (pin "11") (pinfunction "I10_11") (pintype "passive"))
      (node (ref "E18") (pin "11") (pinfunction "I10_11") (pintype "passive"))
    )
    (net (code "82") (name "Net-(E15A-CLK)") (class "Default")
      (node (ref "E15") (pin "11") (pinfunction "CLK_11") (pintype "input"))
      (node (ref "E15") (pin "3") (pinfunction "CLK_3") (pintype "input"))
      (node (ref "U$1") (pin "AU1") (pinfunction "1_AU1") (pintype "bidirectional"))
    )
    (net (code "83") (name "Net-(E15A-D)") (class "Default")
      (node (ref "E1") (pin "8") (pinfunction "O_8") (pintype "output"))
      (node (ref "E15") (pin "2") (pinfunction "D_2") (pintype "input"))
      (node (ref "E6") (pin "2") (pinfunction "D_2") (pintype "input"))
      (node (ref "E7") (pin "2") (pinfunction "D_2") (pintype "input"))
      (node (ref "E8") (pin "2") (pinfunction "D_2") (pintype "input"))
      (node (ref "U$1") (pin "AJ1") (pinfunction "1_AJ1") (pintype "bidirectional"))
    )
    (net (code "84") (name "Net-(E15B-D)") (class "Default")
      (node (ref "E15") (pin "12") (pinfunction "D_12") (pintype "input"))
      (node (ref "E2") (pin "8") (pinfunction "O_8") (pintype "output"))
      (node (ref "E6") (pin "12") (pinfunction "D_12") (pintype "input"))
      (node (ref "E7") (pin "12") (pinfunction "D_12") (pintype "input"))
      (node (ref "E8") (pin "12") (pinfunction "D_12") (pintype "input"))
      (node (ref "U$1") (pin "AK2") (pinfunction "1_AK2") (pintype "bidirectional"))
    )
    (net (code "85") (name "VCC") (class "Default")
      (node (ref "C1") (pin "+") (pinfunction "+_+") (pintype "passive"))
      (node (ref "C2") (pin "+") (pinfunction "+_+") (pintype "passive"))
      (node (ref "C3") (pin "+") (pinfunction "+_+") (pintype "passive"))
      (node (ref "C4") (pin "+") (pinfunction "+_+") (pintype "passive"))
      (node (ref "C5") (pin "+") (pinfunction "+_+") (pintype "passive"))
      (node (ref "C6") (pin "+") (pinfunction "+_+") (pintype "passive"))
      (node (ref "C7") (pin "+") (pinfunction "+_+") (pintype "passive"))
      (node (ref "C8") (pin "+") (pinfunction "+_+") (pintype "passive"))
      (node (ref "R1") (pin "2") (pinfunction "2_2") (pintype "passive"))
      (node (ref "R2") (pin "2") (pinfunction "2_2") (pintype "passive"))
      (node (ref "U$1") (pin "AA2") (pinfunction "1_AA2") (pintype "bidirectional"))
      (node (ref "U$1") (pin "BA2") (pinfunction "1_BA2") (pintype "bidirectional"))
    )
    (net (code "86") (name "unconnected-(E6A-CLR-Pad1)") (class "Default")
      (node (ref "E6") (pin "1") (pinfunction "CLR_1") (pintype "input"))
    )
    (net (code "87") (name "unconnected-(E6A-PRE-Pad4)") (class "Default")
      (node (ref "E6") (pin "4") (pinfunction "PRE_4") (pintype "input"))
    )
    (net (code "88") (name "unconnected-(E6B-CLR-Pad13)") (class "Default")
      (node (ref "E6") (pin "13") (pinfunction "CLR_13") (pintype "input"))
    )
    (net (code "89") (name "unconnected-(E6B-PRE-Pad10)") (class "Default")
      (node (ref "E6") (pin "10") (pinfunction "PRE_10") (pintype "input"))
    )
    (net (code "90") (name "unconnected-(E7A-CLR-Pad1)") (class "Default")
      (node (ref "E7") (pin "1") (pinfunction "CLR_1") (pintype "input"))
    )
    (net (code "91") (name "unconnected-(E7A-PRE-Pad4)") (class "Default")
      (node (ref "E7") (pin "4") (pinfunction "PRE_4") (pintype "input"))
    )
    (net (code "92") (name "unconnected-(E7B-CLR-Pad13)") (class "Default")
      (node (ref "E7") (pin "13") (pinfunction "CLR_13") (pintype "input"))
    )
    (net (code "93") (name "unconnected-(E7B-PRE-Pad10)") (class "Default")
      (node (ref "E7") (pin "10") (pinfunction "PRE_10") (pintype "input"))
    )
    (net (code "94") (name "unconnected-(E8A-CLR-Pad1)") (class "Default")
      (node (ref "E8") (pin "1") (pinfunction "CLR_1") (pintype "input"))
    )
    (net (code "95") (name "unconnected-(E8A-PRE-Pad4)") (class "Default")
      (node (ref "E8") (pin "4") (pinfunction "PRE_4") (pintype "input"))
    )
    (net (code "96") (name "unconnected-(E8B-CLR-Pad13)") (class "Default")
      (node (ref "E8") (pin "13") (pinfunction "CLR_13") (pintype "input"))
    )
    (net (code "97") (name "unconnected-(E8B-PRE-Pad10)") (class "Default")
      (node (ref "E8") (pin "10") (pinfunction "PRE_10") (pintype "input"))
    )
    (net (code "98") (name "unconnected-(E12A-O-Pad8)") (class "Default")
      (node (ref "E12") (pin "8") (pinfunction "O_8") (pintype "output"))
    )
    (net (code "99") (name "unconnected-(E14A-O-Pad8)") (class "Default")
      (node (ref "E14") (pin "8") (pinfunction "O_8") (pintype "output"))
    )
    (net (code "100") (name "unconnected-(E15A-CLR-Pad1)") (class "Default")
      (node (ref "E15") (pin "1") (pinfunction "CLR_1") (pintype "input"))
    )
    (net (code "101") (name "unconnected-(E15A-PRE-Pad4)") (class "Default")
      (node (ref "E15") (pin "4") (pinfunction "PRE_4") (pintype "input"))
    )
    (net (code "102") (name "unconnected-(E15B-CLR-Pad13)") (class "Default")
      (node (ref "E15") (pin "13") (pinfunction "CLR_13") (pintype "input"))
    )
    (net (code "103") (name "unconnected-(E15B-PRE-Pad10)") (class "Default")
      (node (ref "E15") (pin "10") (pinfunction "PRE_10") (pintype "input"))
    )
    (net (code "104") (name "unconnected-(E16A-I9-Pad12)") (class "Default")
      (node (ref "E16") (pin "12") (pinfunction "I9_12") (pintype "passive"))
    )
    (net (code "105") (name "unconnected-(E16A-I10-Pad11)") (class "Default")
      (node (ref "E16") (pin "11") (pinfunction "I10_11") (pintype "passive"))
    )
    (net (code "106") (name "unconnected-(E17A-I9-Pad12)") (class "Default")
      (node (ref "E17") (pin "12") (pinfunction "I9_12") (pintype "passive"))
    )
    (net (code "107") (name "unconnected-(E17A-I10-Pad11)") (class "Default")
      (node (ref "E17") (pin "11") (pinfunction "I10_11") (pintype "passive"))
    )
  )
)
